# GD_Tcontroller_Relay.net
KiCad netlist of a schematic drawn in Altium Designer
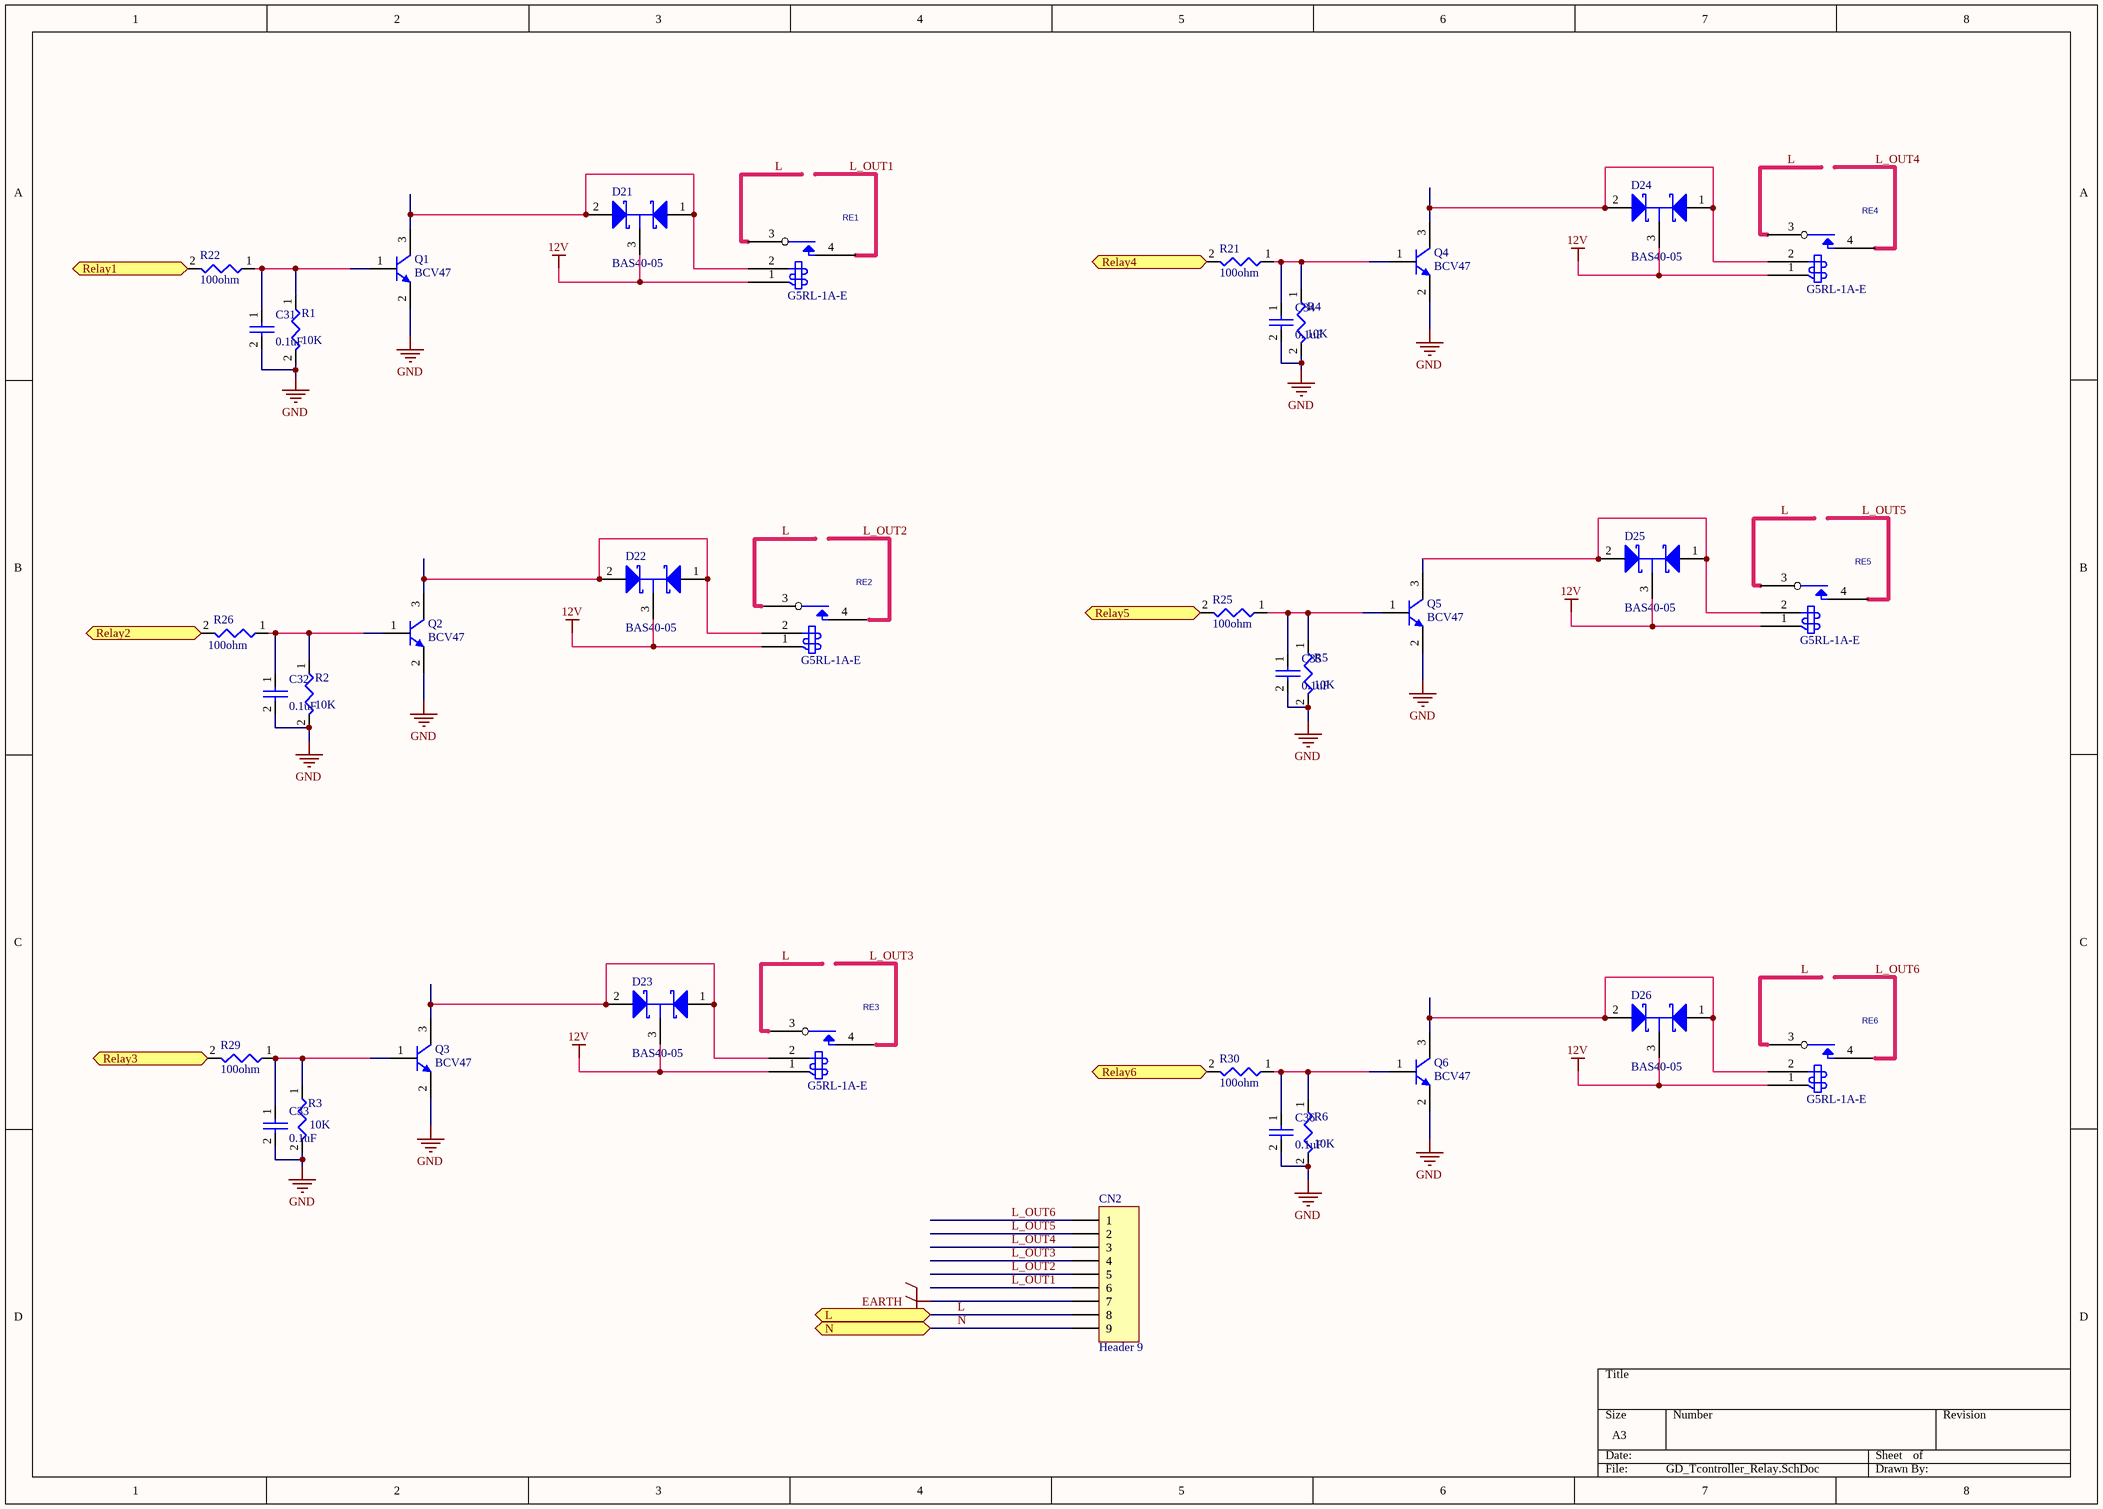
[diagram p0: GD_Tcontroller_Relay.SchDoc]

(export (version "E")
  (design (tool "Eeschema 10.0.6"))
  (components
    (comp (ref "C31")
      (value "0.1uF")
      (footprint "C0805")
      (description "CAP SMD CR X7R 50V 10% 0.1uF 0805 ROHS")
      (fields (field (name "MANUFACTURER") "YAGEO") (field (name "Comment") "CAP"))
      (libsource (lib "enlogic") (part "CAP"))
    )
    (comp (ref "C32")
      (value "0.1uF")
      (footprint "C0805")
      (description "CAP SMD CR X7R 50V 10% 0.1uF 0805 ROHS")
      (fields (field (name "MANUFACTURER") "YAGEO") (field (name "Comment") "CAP"))
      (libsource (lib "enlogic") (part "CAP"))
    )
    (comp (ref "C33")
      (value "0.1uF")
      (footprint "C0805")
      (description "CAP SMD CR X7R 50V 10% 0.1uF 0805 ROHS")
      (fields (field (name "MANUFACTURER") "YAGEO") (field (name "Comment") "CAP"))
      (libsource (lib "enlogic") (part "CAP"))
    )
    (comp (ref "C34")
      (value "0.1uF")
      (footprint "C0805")
      (description "CAP SMD CR X7R 50V 10% 0.1uF 0805 ROHS")
      (fields (field (name "MANUFACTURER") "YAGEO") (field (name "Comment") "CAP"))
      (libsource (lib "enlogic") (part "CAP"))
    )
    (comp (ref "C35")
      (value "0.1uF")
      (footprint "C0805")
      (description "CAP SMD CR X7R 50V 10% 0.1uF 0805 ROHS")
      (fields (field (name "MANUFACTURER") "YAGEO") (field (name "Comment") "CAP"))
      (libsource (lib "enlogic") (part "CAP"))
    )
    (comp (ref "C36")
      (value "0.1uF")
      (footprint "C0805")
      (description "CAP SMD CR X7R 50V 10% 0.1uF 0805 ROHS")
      (fields (field (name "MANUFACTURER") "YAGEO") (field (name "Comment") "CAP"))
      (libsource (lib "enlogic") (part "CAP"))
    )
    (comp (ref "CN2")
      (value "Header 9")
      (footprint "KF7.62-9P")
      (description "Header, 9-Pin")
      (libsource (lib "Enlogic_CN") (part "Header 9"))
    )
    (comp (ref "D21")
      (value "BAS40-05")
      (footprint "SOT23-123")
      (description "DIODE Schottky Diode 40V 0.2A SOT-23 SMD ROHS")
      (fields (field (name "MANUFACTURER") "NXP"))
      (libsource (lib "enlogic") (part "BAS40-05"))
    )
    (comp (ref "D22")
      (value "BAS40-05")
      (footprint "SOT23-123")
      (description "DIODE Schottky Diode 40V 0.2A SOT-23 SMD ROHS")
      (fields (field (name "MANUFACTURER") "NXP"))
      (libsource (lib "enlogic") (part "BAS40-05"))
    )
    (comp (ref "D23")
      (value "BAS40-05")
      (footprint "SOT23-123")
      (description "DIODE Schottky Diode 40V 0.2A SOT-23 SMD ROHS")
      (fields (field (name "MANUFACTURER") "NXP"))
      (libsource (lib "enlogic") (part "BAS40-05"))
    )
    (comp (ref "D24")
      (value "BAS40-05")
      (footprint "SOT23-123")
      (description "DIODE Schottky Diode 40V 0.2A SOT-23 SMD ROHS")
      (fields (field (name "MANUFACTURER") "NXP"))
      (libsource (lib "enlogic") (part "BAS40-05"))
    )
    (comp (ref "D25")
      (value "BAS40-05")
      (footprint "SOT23-123")
      (description "DIODE Schottky Diode 40V 0.2A SOT-23 SMD ROHS")
      (fields (field (name "MANUFACTURER") "NXP"))
      (libsource (lib "enlogic") (part "BAS40-05"))
    )
    (comp (ref "D26")
      (value "BAS40-05")
      (footprint "SOT23-123")
      (description "DIODE Schottky Diode 40V 0.2A SOT-23 SMD ROHS")
      (fields (field (name "MANUFACTURER") "NXP"))
      (libsource (lib "enlogic") (part "BAS40-05"))
    )
    (comp (ref "Q1")
      (value "BCV47")
      (footprint "INF-SOT23_L")
      (description "NPN Silicon Darlington Transistor, 60 V VCEO, 500 mA IC, SOT23, Reel, Green")
      (fields (field (name "MANUFACTURER") "Infineon"))
      (libsource (lib "Altium Content Vault") (part "CMP-1196-00014-1"))
    )
    (comp (ref "Q2")
      (value "BCV47")
      (footprint "INF-SOT23_L")
      (description "NPN Silicon Darlington Transistor, 60 V VCEO, 500 mA IC, SOT23, Reel, Green")
      (fields (field (name "MANUFACTURER") "Infineon"))
      (libsource (lib "Altium Content Vault") (part "CMP-1196-00014-1"))
    )
    (comp (ref "Q3")
      (value "BCV47")
      (footprint "INF-SOT23_L")
      (description "NPN Silicon Darlington Transistor, 60 V VCEO, 500 mA IC, SOT23, Reel, Green")
      (fields (field (name "MANUFACTURER") "Infineon"))
      (libsource (lib "Altium Content Vault") (part "CMP-1196-00014-1"))
    )
    (comp (ref "Q4")
      (value "BCV47")
      (footprint "INF-SOT23_L")
      (description "NPN Silicon Darlington Transistor, 60 V VCEO, 500 mA IC, SOT23, Reel, Green")
      (fields (field (name "MANUFACTURER") "Infineon"))
      (libsource (lib "Altium Content Vault") (part "CMP-1196-00014-1"))
    )
    (comp (ref "Q5")
      (value "BCV47")
      (footprint "INF-SOT23_L")
      (description "NPN Silicon Darlington Transistor, 60 V VCEO, 500 mA IC, SOT23, Reel, Green")
      (fields (field (name "MANUFACTURER") "Infineon"))
      (libsource (lib "Altium Content Vault") (part "CMP-1196-00014-1"))
    )
    (comp (ref "Q6")
      (value "BCV47")
      (footprint "INF-SOT23_L")
      (description "NPN Silicon Darlington Transistor, 60 V VCEO, 500 mA IC, SOT23, Reel, Green")
      (fields (field (name "MANUFACTURER") "Infineon"))
      (libsource (lib "Altium Content Vault") (part "CMP-1196-00014-1"))
    )
    (comp (ref "R1")
      (value "10K")
      (footprint "R0805")
      (description "RES THICK_FILM SMD 10K ohm 5% 1/10W ROHS 0603")
      (fields (field (name "MANUFACTURER") "YAGEO"))
      (libsource (lib "Enlogic") (part "RES"))
    )
    (comp (ref "R2")
      (value "10K")
      (footprint "R0805")
      (description "RES THICK_FILM SMD 10K ohm 5% 1/10W ROHS 0603")
      (fields (field (name "MANUFACTURER") "YAGEO"))
      (libsource (lib "Enlogic") (part "RES"))
    )
    (comp (ref "R3")
      (value "10K")
      (footprint "R0805")
      (description "RES THICK_FILM SMD 10K ohm 5% 1/10W ROHS 0603")
      (fields (field (name "MANUFACTURER") "YAGEO"))
      (libsource (lib "Enlogic") (part "RES"))
    )
    (comp (ref "R4")
      (value "10K")
      (footprint "R0805")
      (description "RES THICK_FILM SMD 10K ohm 5% 1/10W ROHS 0603")
      (fields (field (name "MANUFACTURER") "YAGEO"))
      (libsource (lib "Enlogic") (part "RES"))
    )
    (comp (ref "R5")
      (value "10K")
      (footprint "R0805")
      (description "RES THICK_FILM SMD 10K ohm 5% 1/10W ROHS 0603")
      (fields (field (name "MANUFACTURER") "YAGEO"))
      (libsource (lib "Enlogic") (part "RES"))
    )
    (comp (ref "R6")
      (value "10K")
      (footprint "R0805")
      (description "RES THICK_FILM SMD 10K ohm 5% 1/10W ROHS 0603")
      (fields (field (name "MANUFACTURER") "YAGEO"))
      (libsource (lib "Enlogic") (part "RES"))
    )
    (comp (ref "R21")
      (value "100ohm")
      (footprint "R0805")
      (description "RES THICK_FILM SMD 100 OHM 5% 1/8W ROHS 0805")
      (fields (field (name "MANUFACTURER") "YAGEO") (field (name "Comment") "RES"))
      (libsource (lib "enlogic") (part "RES"))
    )
    (comp (ref "R22")
      (value "100ohm")
      (footprint "R0805")
      (description "RES THICK_FILM SMD 100 OHM 5% 1/8W ROHS 0805")
      (fields (field (name "MANUFACTURER") "YAGEO") (field (name "Comment") "RES"))
      (libsource (lib "enlogic") (part "RES"))
    )
    (comp (ref "R25")
      (value "100ohm")
      (footprint "R0805")
      (description "RES THICK_FILM SMD 100 OHM 5% 1/8W ROHS 0805")
      (fields (field (name "MANUFACTURER") "YAGEO") (field (name "Comment") "RES"))
      (libsource (lib "enlogic") (part "RES"))
    )
    (comp (ref "R26")
      (value "100ohm")
      (footprint "R0805")
      (description "RES THICK_FILM SMD 100 OHM 5% 1/8W ROHS 0805")
      (fields (field (name "MANUFACTURER") "YAGEO") (field (name "Comment") "RES"))
      (libsource (lib "enlogic") (part "RES"))
    )
    (comp (ref "R29")
      (value "100ohm")
      (footprint "R0805")
      (description "RES THICK_FILM SMD 100 OHM 5% 1/8W ROHS 0805")
      (fields (field (name "MANUFACTURER") "YAGEO") (field (name "Comment") "RES"))
      (libsource (lib "enlogic") (part "RES"))
    )
    (comp (ref "R30")
      (value "100ohm")
      (footprint "R0805")
      (description "RES THICK_FILM SMD 100 OHM 5% 1/8W ROHS 0805")
      (fields (field (name "MANUFACTURER") "YAGEO") (field (name "Comment") "RES"))
      (libsource (lib "enlogic") (part "RES"))
    )
    (comp (ref "RE1")
      (value "RELAY SP")
      (footprint "G5RL-1A-E")
      (description "Relay,12VDC,16A,250VAC")
      (fields (field (name "MANUFACTURER") "OMRON") (field (name "MANUFACTURER P/N") "G5RL-1A-E"))
      (libsource (lib "enlogic") (part "RELAY SP"))
    )
    (comp (ref "RE2")
      (value "RELAY SP")
      (footprint "G5RL-1A-E")
      (description "Relay,12VDC,16A,250VAC")
      (fields (field (name "MANUFACTURER") "OMRON") (field (name "MANUFACTURER P/N") "G5RL-1A-E"))
      (libsource (lib "enlogic") (part "RELAY SP"))
    )
    (comp (ref "RE3")
      (value "RELAY SP")
      (footprint "G5RL-1A-E")
      (description "Relay,12VDC,16A,250VAC")
      (fields (field (name "MANUFACTURER") "OMRON") (field (name "MANUFACTURER P/N") "G5RL-1A-E"))
      (libsource (lib "enlogic") (part "RELAY SP"))
    )
    (comp (ref "RE4")
      (value "RELAY SP")
      (footprint "G5RL-1A-E")
      (description "Relay,12VDC,16A,250VAC")
      (fields (field (name "MANUFACTURER") "OMRON") (field (name "MANUFACTURER P/N") "G5RL-1A-E"))
      (libsource (lib "enlogic") (part "RELAY SP"))
    )
    (comp (ref "RE5")
      (value "RELAY SP")
      (footprint "G5RL-1A-E")
      (description "Relay,12VDC,16A,250VAC")
      (fields (field (name "MANUFACTURER") "OMRON") (field (name "MANUFACTURER P/N") "G5RL-1A-E"))
      (libsource (lib "enlogic") (part "RELAY SP"))
    )
    (comp (ref "RE6")
      (value "RELAY SP")
      (footprint "G5RL-1A-E")
      (description "Relay,12VDC,16A,250VAC")
      (fields (field (name "MANUFACTURER") "OMRON") (field (name "MANUFACTURER P/N") "G5RL-1A-E"))
      (libsource (lib "enlogic") (part "RELAY SP"))
    )
  )
  (nets
    (net (code "1") (name "/L") (class "Default")
      (node (ref "CN2") (pin "8") (pinfunction "8_8") (pintype "passive"))
      (node (ref "RE1") (pin "3") (pinfunction "COMMON_3") (pintype "passive"))
      (node (ref "RE2") (pin "3") (pinfunction "COMMON_3") (pintype "passive"))
      (node (ref "RE3") (pin "3") (pinfunction "COMMON_3") (pintype "passive"))
      (node (ref "RE4") (pin "3") (pinfunction "COMMON_3") (pintype "passive"))
      (node (ref "RE5") (pin "3") (pinfunction "COMMON_3") (pintype "passive"))
      (node (ref "RE6") (pin "3") (pinfunction "COMMON_3") (pintype "passive"))
    )
    (net (code "2") (name "/L_OUT1") (class "Default")
      (node (ref "CN2") (pin "6") (pinfunction "6_6") (pintype "passive"))
      (node (ref "RE1") (pin "4") (pinfunction "NO_4") (pintype "passive"))
    )
    (net (code "3") (name "/L_OUT2") (class "Default")
      (node (ref "CN2") (pin "5") (pinfunction "5_5") (pintype "passive"))
      (node (ref "RE2") (pin "4") (pinfunction "NO_4") (pintype "passive"))
    )
    (net (code "4") (name "/L_OUT3") (class "Default")
      (node (ref "CN2") (pin "4") (pinfunction "4_4") (pintype "passive"))
      (node (ref "RE3") (pin "4") (pinfunction "NO_4") (pintype "passive"))
    )
    (net (code "5") (name "/L_OUT4") (class "Default")
      (node (ref "CN2") (pin "3") (pinfunction "3_3") (pintype "passive"))
      (node (ref "RE4") (pin "4") (pinfunction "NO_4") (pintype "passive"))
    )
    (net (code "6") (name "/L_OUT5") (class "Default")
      (node (ref "CN2") (pin "2") (pinfunction "2_2") (pintype "passive"))
      (node (ref "RE5") (pin "4") (pinfunction "NO_4") (pintype "passive"))
    )
    (net (code "7") (name "/L_OUT6") (class "Default")
      (node (ref "CN2") (pin "1") (pinfunction "1_1") (pintype "passive"))
      (node (ref "RE6") (pin "4") (pinfunction "NO_4") (pintype "passive"))
    )
    (net (code "8") (name "/N") (class "Default")
      (node (ref "CN2") (pin "9") (pinfunction "9_9") (pintype "passive"))
    )
    (net (code "9") (name "/Relay1") (class "Default")
      (node (ref "R22") (pin "2") (pinfunction "2_2") (pintype "passive"))
    )
    (net (code "10") (name "/Relay2") (class "Default")
      (node (ref "R26") (pin "2") (pinfunction "2_2") (pintype "passive"))
    )
    (net (code "11") (name "/Relay3") (class "Default")
      (node (ref "R29") (pin "2") (pinfunction "2_2") (pintype "passive"))
    )
    (net (code "12") (name "/Relay4") (class "Default")
      (node (ref "R21") (pin "2") (pinfunction "2_2") (pintype "passive"))
    )
    (net (code "13") (name "/Relay5") (class "Default")
      (node (ref "R25") (pin "2") (pinfunction "2_2") (pintype "passive"))
    )
    (net (code "14") (name "/Relay6") (class "Default")
      (node (ref "R30") (pin "2") (pinfunction "2_2") (pintype "passive"))
    )
    (net (code "15") (name "12V") (class "Default")
      (node (ref "D21") (pin "3") (pinfunction "C_3") (pintype "passive"))
      (node (ref "D22") (pin "3") (pinfunction "C_3") (pintype "passive"))
      (node (ref "D23") (pin "3") (pinfunction "C_3") (pintype "passive"))
      (node (ref "D24") (pin "3") (pinfunction "C_3") (pintype "passive"))
      (node (ref "D25") (pin "3") (pinfunction "C_3") (pintype "passive"))
      (node (ref "D26") (pin "3") (pinfunction "C_3") (pintype "passive"))
      (node (ref "RE1") (pin "1") (pinfunction "COIL_1") (pintype "passive"))
      (node (ref "RE2") (pin "1") (pinfunction "COIL_1") (pintype "passive"))
      (node (ref "RE3") (pin "1") (pinfunction "COIL_1") (pintype "passive"))
      (node (ref "RE4") (pin "1") (pinfunction "COIL_1") (pintype "passive"))
      (node (ref "RE5") (pin "1") (pinfunction "COIL_1") (pintype "passive"))
      (node (ref "RE6") (pin "1") (pinfunction "COIL_1") (pintype "passive"))
    )
    (net (code "16") (name "EARTH") (class "Default")
      (node (ref "CN2") (pin "7") (pinfunction "7_7") (pintype "passive"))
    )
    (net (code "17") (name "GND") (class "Default")
      (node (ref "C31") (pin "2") (pinfunction "2_2") (pintype "passive"))
      (node (ref "C32") (pin "2") (pinfunction "2_2") (pintype "passive"))
      (node (ref "C33") (pin "2") (pinfunction "2_2") (pintype "passive"))
      (node (ref "C34") (pin "2") (pinfunction "2_2") (pintype "passive"))
      (node (ref "C35") (pin "2") (pinfunction "2_2") (pintype "passive"))
      (node (ref "C36") (pin "2") (pinfunction "2_2") (pintype "passive"))
      (node (ref "Q1") (pin "2") (pinfunction "E_2") (pintype "passive"))
      (node (ref "Q2") (pin "2") (pinfunction "E_2") (pintype "passive"))
      (node (ref "Q3") (pin "2") (pinfunction "E_2") (pintype "passive"))
      (node (ref "Q4") (pin "2") (pinfunction "E_2") (pintype "passive"))
      (node (ref "Q5") (pin "2") (pinfunction "E_2") (pintype "passive"))
      (node (ref "Q6") (pin "2") (pinfunction "E_2") (pintype "passive"))
      (node (ref "R1") (pin "2") (pinfunction "2_2") (pintype "passive"))
      (node (ref "R2") (pin "2") (pinfunction "2_2") (pintype "passive"))
      (node (ref "R3") (pin "2") (pinfunction "2_2") (pintype "passive"))
      (node (ref "R4") (pin "2") (pinfunction "2_2") (pintype "passive"))
      (node (ref "R5") (pin "2") (pinfunction "2_2") (pintype "passive"))
      (node (ref "R6") (pin "2") (pinfunction "2_2") (pintype "passive"))
    )
    (net (code "18") (name "Net-(D21-A)") (class "Default")
      (node (ref "D21") (pin "1") (pinfunction "A_1") (pintype "passive"))
      (node (ref "D21") (pin "2") (pinfunction "K_2") (pintype "passive"))
      (node (ref "Q1") (pin "3") (pinfunction "C_3") (pintype "passive"))
      (node (ref "RE1") (pin "2") (pinfunction "COIL_2") (pintype "passive"))
    )
    (net (code "19") (name "Net-(D22-A)") (class "Default")
      (node (ref "D22") (pin "1") (pinfunction "A_1") (pintype "passive"))
      (node (ref "D22") (pin "2") (pinfunction "K_2") (pintype "passive"))
      (node (ref "Q2") (pin "3") (pinfunction "C_3") (pintype "passive"))
      (node (ref "RE2") (pin "2") (pinfunction "COIL_2") (pintype "passive"))
    )
    (net (code "20") (name "Net-(D23-A)") (class "Default")
      (node (ref "D23") (pin "1") (pinfunction "A_1") (pintype "passive"))
      (node (ref "D23") (pin "2") (pinfunction "K_2") (pintype "passive"))
      (node (ref "Q3") (pin "3") (pinfunction "C_3") (pintype "passive"))
      (node (ref "RE3") (pin "2") (pinfunction "COIL_2") (pintype "passive"))
    )
    (net (code "21") (name "Net-(D24-A)") (class "Default")
      (node (ref "D24") (pin "1") (pinfunction "A_1") (pintype "passive"))
      (node (ref "D24") (pin "2") (pinfunction "K_2") (pintype "passive"))
      (node (ref "Q4") (pin "3") (pinfunction "C_3") (pintype "passive"))
      (node (ref "RE4") (pin "2") (pinfunction "COIL_2") (pintype "passive"))
    )
    (net (code "22") (name "Net-(D25-A)") (class "Default")
      (node (ref "D25") (pin "1") (pinfunction "A_1") (pintype "passive"))
      (node (ref "D25") (pin "2") (pinfunction "K_2") (pintype "passive"))
      (node (ref "Q5") (pin "3") (pinfunction "C_3") (pintype "passive"))
      (node (ref "RE5") (pin "2") (pinfunction "COIL_2") (pintype "passive"))
    )
    (net (code "23") (name "Net-(D26-A)") (class "Default")
      (node (ref "D26") (pin "1") (pinfunction "A_1") (pintype "passive"))
      (node (ref "D26") (pin "2") (pinfunction "K_2") (pintype "passive"))
      (node (ref "Q6") (pin "3") (pinfunction "C_3") (pintype "passive"))
      (node (ref "RE6") (pin "2") (pinfunction "COIL_2") (pintype "passive"))
    )
    (net (code "24") (name "Net-(Q1-B)") (class "Default")
      (node (ref "C31") (pin "1") (pinfunction "1_1") (pintype "passive"))
      (node (ref "Q1") (pin "1") (pinfunction "B_1") (pintype "passive"))
      (node (ref "R1") (pin "1") (pinfunction "1_1") (pintype "passive"))
      (node (ref "R22") (pin "1") (pinfunction "1_1") (pintype "passive"))
    )
    (net (code "25") (name "Net-(Q2-B)") (class "Default")
      (node (ref "C32") (pin "1") (pinfunction "1_1") (pintype "passive"))
      (node (ref "Q2") (pin "1") (pinfunction "B_1") (pintype "passive"))
      (node (ref "R2") (pin "1") (pinfunction "1_1") (pintype "passive"))
      (node (ref "R26") (pin "1") (pinfunction "1_1") (pintype "passive"))
    )
    (net (code "26") (name "Net-(Q3-B)") (class "Default")
      (node (ref "C33") (pin "1") (pinfunction "1_1") (pintype "passive"))
      (node (ref "Q3") (pin "1") (pinfunction "B_1") (pintype "passive"))
      (node (ref "R29") (pin "1") (pinfunction "1_1") (pintype "passive"))
      (node (ref "R3") (pin "1") (pinfunction "1_1") (pintype "passive"))
    )
    (net (code "27") (name "Net-(Q4-B)") (class "Default")
      (node (ref "C34") (pin "1") (pinfunction "1_1") (pintype "passive"))
      (node (ref "Q4") (pin "1") (pinfunction "B_1") (pintype "passive"))
      (node (ref "R21") (pin "1") (pinfunction "1_1") (pintype "passive"))
      (node (ref "R4") (pin "1") (pinfunction "1_1") (pintype "passive"))
    )
    (net (code "28") (name "Net-(Q5-B)") (class "Default")
      (node (ref "C35") (pin "1") (pinfunction "1_1") (pintype "passive"))
      (node (ref "Q5") (pin "1") (pinfunction "B_1") (pintype "passive"))
      (node (ref "R25") (pin "1") (pinfunction "1_1") (pintype "passive"))
      (node (ref "R5") (pin "1") (pinfunction "1_1") (pintype "passive"))
    )
    (net (code "29") (name "Net-(Q6-B)") (class "Default")
      (node (ref "C36") (pin "1") (pinfunction "1_1") (pintype "passive"))
      (node (ref "Q6") (pin "1") (pinfunction "B_1") (pintype "passive"))
      (node (ref "R30") (pin "1") (pinfunction "1_1") (pintype "passive"))
      (node (ref "R6") (pin "1") (pinfunction "1_1") (pintype "passive"))
    )
  )
)
